# LPC812_breakout_v2_0.net
KiCad netlist of a schematic drawn in EAGLE
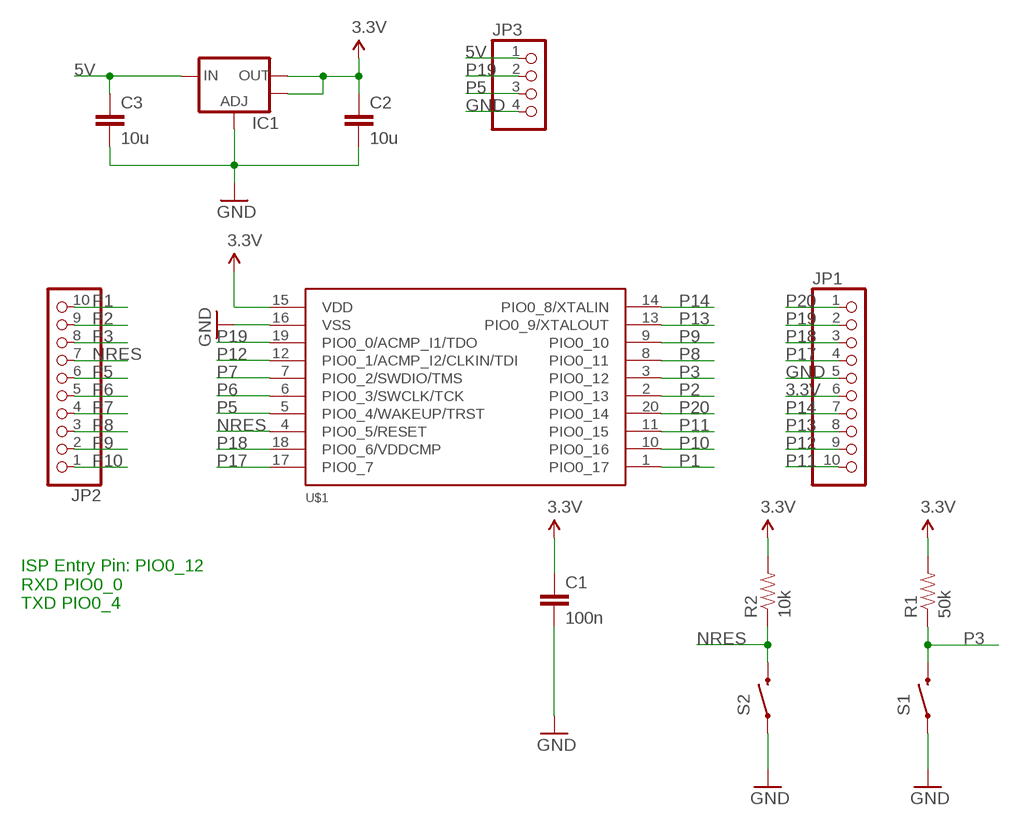
[diagram p0: schematic, sheet 1]

(export (version "E")
  (design (tool "Eeschema 10.0.6"))
  (components
    (comp (ref "C1")
      (value "100n")
      (footprint "eagle-import:0805")
      (libsource (lib "eagle-import") (part "CAP0805"))
    )
    (comp (ref "C2")
      (value "10u")
      (footprint "eagle-import:0805")
      (libsource (lib "eagle-import") (part "CAP0805"))
    )
    (comp (ref "C3")
      (value "10u")
      (footprint "eagle-import:0805")
      (libsource (lib "eagle-import") (part "CAP0805"))
    )
    (comp (ref "IC1")
      (value "V_REG_LM1117SOT223")
      (footprint "eagle-import:SOT223")
      (libsource (lib "eagle-import") (part "V_REG_LM1117SOT223"))
    )
    (comp (ref "JP1")
      (value "HEADER-1X10ROUND")
      (footprint "eagle-import:1X10_ROUND")
      (libsource (lib "eagle-import") (part "HEADER-1X10ROUND"))
    )
    (comp (ref "JP2")
      (value "HEADER-1X10ROUND")
      (footprint "eagle-import:1X10_ROUND")
      (libsource (lib "eagle-import") (part "HEADER-1X10ROUND"))
    )
    (comp (ref "JP3")
      (value "HEADER-1X4ROUND")
      (footprint "eagle-import:1X04_ROUND")
      (libsource (lib "eagle-import") (part "HEADER-1X4ROUND"))
    )
    (comp (ref "R1")
      (value "50k")
      (footprint "eagle-import:0805")
      (libsource (lib "eagle-import") (part "RESISTOR0805-RES"))
    )
    (comp (ref "R2")
      (value "10k")
      (footprint "eagle-import:0805")
      (libsource (lib "eagle-import") (part "RESISTOR0805-RES"))
    )
    (comp (ref "S1")
      (value "SWITCH-MOMENTARY-2-SMD-1101NE")
      (footprint "eagle-import:TACTILE-SWITCH-1101NE")
      (libsource (lib "eagle-import") (part "SWITCH-MOMENTARY-2-SMD-1101NE"))
    )
    (comp (ref "S2")
      (value "SWITCH-MOMENTARY-2-SMD-1101NE")
      (footprint "eagle-import:TACTILE-SWITCH-1101NE")
      (libsource (lib "eagle-import") (part "SWITCH-MOMENTARY-2-SMD-1101NE"))
    )
    (comp (ref "U$1")
      (value "LPC812M101JDH20")
      (footprint "eagle-import:TSSOP20")
      (libsource (lib "eagle-import") (part "LPC812M101JDH20"))
    )
  )
  (nets
    (net (code "1") (name "/5V") (class "Default")
      (node (ref "C3") (pin "1") (pinfunction "1_1") (pintype "passive"))
      (node (ref "IC1") (pin "3") (pinfunction "IN_3") (pintype "input"))
      (node (ref "JP3") (pin "1") (pinfunction "1_1") (pintype "passive"))
    )
    (net (code "2") (name "/NRES") (class "Default")
      (node (ref "JP2") (pin "7") (pinfunction "7_7") (pintype "passive"))
      (node (ref "R2") (pin "1") (pinfunction "1_1") (pintype "passive"))
      (node (ref "S2") (pin "P$2") (pinfunction "2_P$2") (pintype "passive"))
      (node (ref "U$1") (pin "4") (pinfunction "PIO0_5/RESET_4") (pintype "bidirectional"))
    )
    (net (code "3") (name "/P1") (class "Default")
      (node (ref "JP2") (pin "10") (pinfunction "10_10") (pintype "passive"))
      (node (ref "U$1") (pin "1") (pinfunction "PIO0_17_1") (pintype "bidirectional"))
    )
    (net (code "4") (name "/P2") (class "Default")
      (node (ref "JP2") (pin "9") (pinfunction "9_9") (pintype "passive"))
      (node (ref "U$1") (pin "2") (pinfunction "PIO0_13_2") (pintype "bidirectional"))
    )
    (net (code "5") (name "/P3") (class "Default")
      (node (ref "JP2") (pin "8") (pinfunction "8_8") (pintype "passive"))
      (node (ref "R1") (pin "1") (pinfunction "1_1") (pintype "passive"))
      (node (ref "S1") (pin "P$2") (pinfunction "2_P$2") (pintype "passive"))
      (node (ref "U$1") (pin "3") (pinfunction "PIO0_12_3") (pintype "bidirectional"))
    )
    (net (code "6") (name "/P5") (class "Default")
      (node (ref "JP2") (pin "6") (pinfunction "6_6") (pintype "passive"))
      (node (ref "JP3") (pin "3") (pinfunction "3_3") (pintype "passive"))
      (node (ref "U$1") (pin "5") (pinfunction "PIO0_4/WAKEUP/TRST_5") (pintype "bidirectional"))
    )
    (net (code "7") (name "/P6") (class "Default")
      (node (ref "JP2") (pin "5") (pinfunction "5_5") (pintype "passive"))
      (node (ref "U$1") (pin "6") (pinfunction "PIO0_3/SWCLK/TCK_6") (pintype "bidirectional"))
    )
    (net (code "8") (name "/P7") (class "Default")
      (node (ref "JP2") (pin "4") (pinfunction "4_4") (pintype "passive"))
      (node (ref "U$1") (pin "7") (pinfunction "PIO0_2/SWDIO/TMS_7") (pintype "bidirectional"))
    )
    (net (code "9") (name "/P8") (class "Default")
      (node (ref "JP2") (pin "3") (pinfunction "3_3") (pintype "passive"))
      (node (ref "U$1") (pin "8") (pinfunction "PIO0_11_8") (pintype "bidirectional"))
    )
    (net (code "10") (name "/P9") (class "Default")
      (node (ref "JP2") (pin "2") (pinfunction "2_2") (pintype "passive"))
      (node (ref "U$1") (pin "9") (pinfunction "PIO0_10_9") (pintype "bidirectional"))
    )
    (net (code "11") (name "/P10") (class "Default")
      (node (ref "JP2") (pin "1") (pinfunction "1_1") (pintype "passive"))
      (node (ref "U$1") (pin "10") (pinfunction "PIO0_16_10") (pintype "bidirectional"))
    )
    (net (code "12") (name "/P11") (class "Default")
      (node (ref "JP1") (pin "10") (pinfunction "10_10") (pintype "passive"))
      (node (ref "U$1") (pin "11") (pinfunction "PIO0_15_11") (pintype "bidirectional"))
    )
    (net (code "13") (name "/P12") (class "Default")
      (node (ref "JP1") (pin "9") (pinfunction "9_9") (pintype "passive"))
      (node (ref "U$1") (pin "12") (pinfunction "PIO0_1/ACMP_I2/CLKIN/TDI_12") (pintype "bidirectional"))
    )
    (net (code "14") (name "/P13") (class "Default")
      (node (ref "JP1") (pin "8") (pinfunction "8_8") (pintype "passive"))
      (node (ref "U$1") (pin "13") (pinfunction "PIO0_9/XTALOUT_13") (pintype "bidirectional"))
    )
    (net (code "15") (name "/P14") (class "Default")
      (node (ref "JP1") (pin "7") (pinfunction "7_7") (pintype "passive"))
      (node (ref "U$1") (pin "14") (pinfunction "PIO0_8/XTALIN_14") (pintype "bidirectional"))
    )
    (net (code "16") (name "/P17") (class "Default")
      (node (ref "JP1") (pin "4") (pinfunction "4_4") (pintype "passive"))
      (node (ref "U$1") (pin "17") (pinfunction "PIO0_7_17") (pintype "bidirectional"))
    )
    (net (code "17") (name "/P18") (class "Default")
      (node (ref "JP1") (pin "3") (pinfunction "3_3") (pintype "passive"))
      (node (ref "U$1") (pin "18") (pinfunction "PIO0_6/VDDCMP_18") (pintype "bidirectional"))
    )
    (net (code "18") (name "/P19") (class "Default")
      (node (ref "JP1") (pin "2") (pinfunction "2_2") (pintype "passive"))
      (node (ref "JP3") (pin "2") (pinfunction "2_2") (pintype "passive"))
      (node (ref "U$1") (pin "19") (pinfunction "PIO0_0/ACMP_I1/TDO_19") (pintype "bidirectional"))
    )
    (net (code "19") (name "/P20") (class "Default")
      (node (ref "JP1") (pin "1") (pinfunction "1_1") (pintype "passive"))
      (node (ref "U$1") (pin "20") (pinfunction "PIO0_14_20") (pintype "bidirectional"))
    )
    (net (code "20") (name "3.3V") (class "Default")
      (node (ref "C1") (pin "1") (pinfunction "1_1") (pintype "passive"))
      (node (ref "C2") (pin "1") (pinfunction "1_1") (pintype "passive"))
      (node (ref "IC1") (pin "2") (pinfunction "OUT_2") (pintype "output"))
      (node (ref "IC1") (pin "4") (pinfunction "OUT_4") (pintype "output"))
      (node (ref "JP1") (pin "6") (pinfunction "6_6") (pintype "passive"))
      (node (ref "R1") (pin "2") (pinfunction "2_2") (pintype "passive"))
      (node (ref "R2") (pin "2") (pinfunction "2_2") (pintype "passive"))
      (node (ref "U$1") (pin "15") (pinfunction "VDD_15") (pintype "bidirectional"))
    )
    (net (code "21") (name "GND") (class "Default")
      (node (ref "C1") (pin "2") (pinfunction "2_2") (pintype "passive"))
      (node (ref "C2") (pin "2") (pinfunction "2_2") (pintype "passive"))
      (node (ref "C3") (pin "2") (pinfunction "2_2") (pintype "passive"))
      (node (ref "IC1") (pin "1") (pinfunction "ADJ_1") (pintype "input"))
      (node (ref "JP1") (pin "5") (pinfunction "5_5") (pintype "passive"))
      (node (ref "JP3") (pin "4") (pinfunction "4_4") (pintype "passive"))
      (node (ref "S1") (pin "P$1") (pinfunction "1_P$1") (pintype "passive"))
      (node (ref "S2") (pin "P$1") (pinfunction "1_P$1") (pintype "passive"))
      (node (ref "U$1") (pin "16") (pinfunction "VSS_16") (pintype "bidirectional"))
    )
  )
)
